# MB1076.net
KiCad netlist of a schematic drawn in Altium Designer
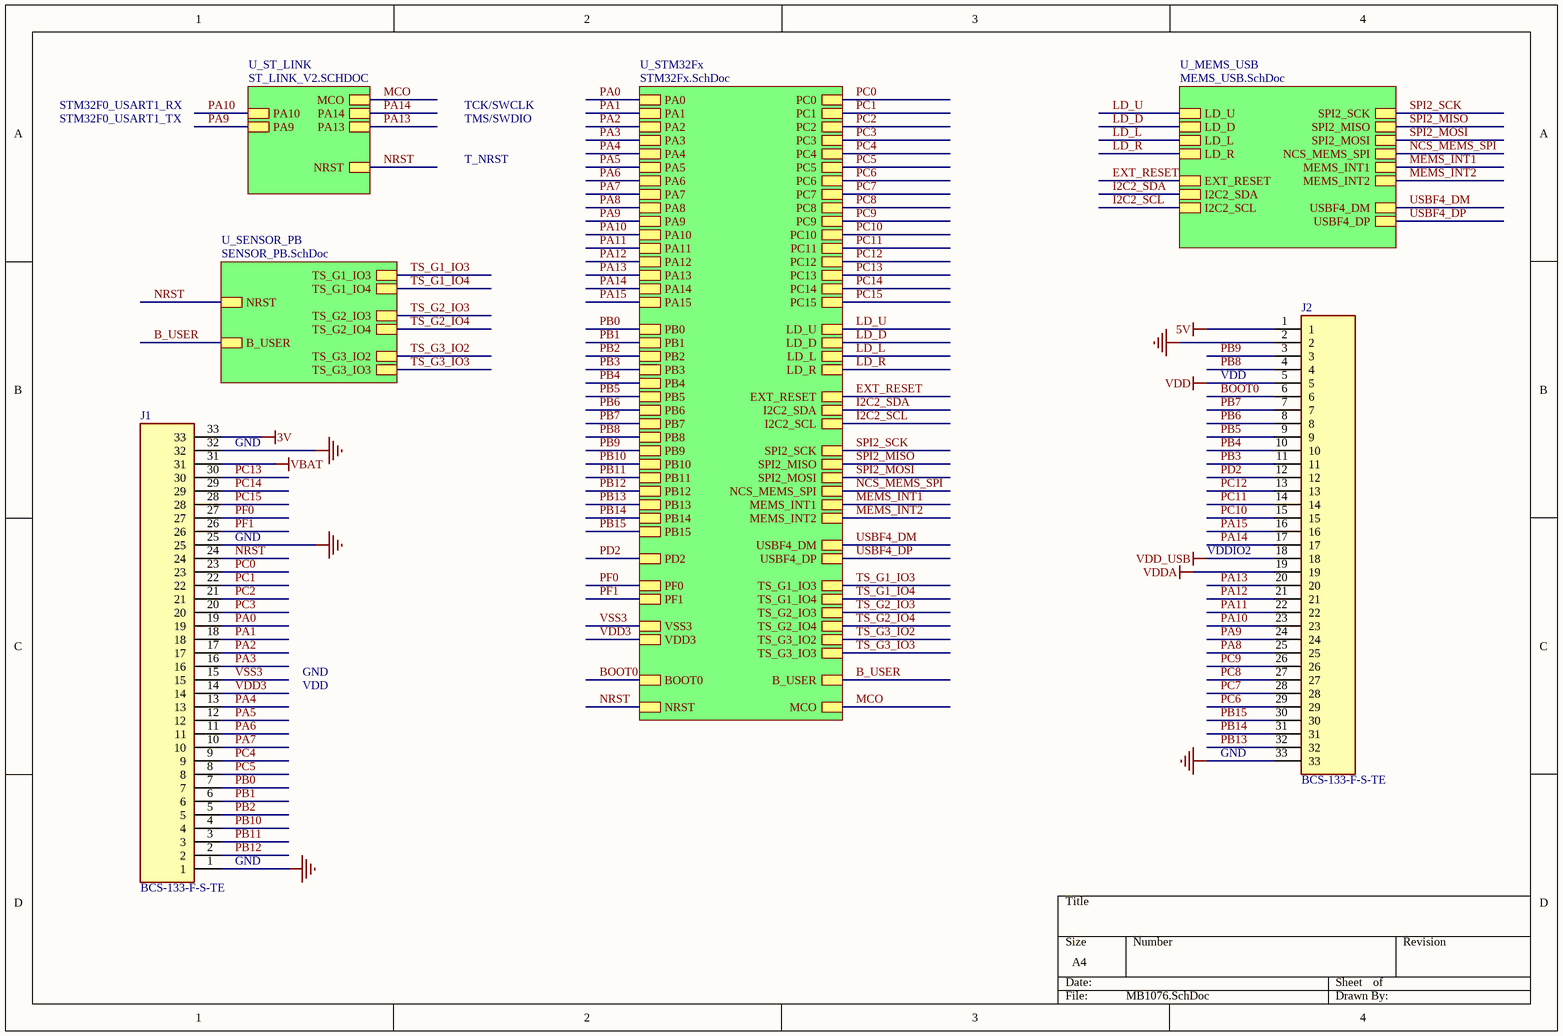
[diagram p0: MB1076.SchDoc]

(export (version "E")
  (design (tool "Eeschema 10.0.6"))
  (components
    (comp (ref "J1")
      (value "BCS-133-F-S-TE")
      (footprint "SamacSys:BCS-133-XXX-S-TE")
      (description "Connector")
      (libsource (lib "*") (part "BCS-133-F-S-TE"))
    )
    (comp (ref "J2")
      (value "BCS-133-F-S-TE")
      (footprint "SamacSys:BCS-133-XXX-S-TE")
      (description "Connector")
      (libsource (lib "") (part "BCS-133-F-S-TE_1"))
    )
  )
  (nets
    (net (code "1") (name "/BOOT0") (class "Default")
      (node (ref "J2") (pin "6") (pinfunction "6_6") (pintype "passive"))
    )
    (net (code "14") (name "/NRST") (class "Default")
      (node (ref "J1") (pin "24") (pinfunction "24_24") (pintype "passive"))
    )
    (net (code "15") (name "/PA0") (class "Default")
      (node (ref "J1") (pin "19") (pinfunction "19_19") (pintype "passive"))
    )
    (net (code "16") (name "/PA1") (class "Default")
      (node (ref "J1") (pin "18") (pinfunction "18_18") (pintype "passive"))
    )
    (net (code "17") (name "/PA2") (class "Default")
      (node (ref "J1") (pin "17") (pinfunction "17_17") (pintype "passive"))
    )
    (net (code "18") (name "/PA3") (class "Default")
      (node (ref "J1") (pin "16") (pinfunction "16_16") (pintype "passive"))
    )
    (net (code "19") (name "/PA4") (class "Default")
      (node (ref "J1") (pin "13") (pinfunction "13_13") (pintype "passive"))
    )
    (net (code "20") (name "/PA5") (class "Default")
      (node (ref "J1") (pin "12") (pinfunction "12_12") (pintype "passive"))
    )
    (net (code "21") (name "/PA6") (class "Default")
      (node (ref "J1") (pin "11") (pinfunction "11_11") (pintype "passive"))
    )
    (net (code "22") (name "/PA7") (class "Default")
      (node (ref "J1") (pin "10") (pinfunction "10_10") (pintype "passive"))
    )
    (net (code "23") (name "/PA8") (class "Default")
      (node (ref "J2") (pin "25") (pinfunction "25_25") (pintype "passive"))
    )
    (net (code "24") (name "/PA9") (class "Default")
      (node (ref "J2") (pin "24") (pinfunction "24_24") (pintype "passive"))
    )
    (net (code "25") (name "/PA10") (class "Default")
      (node (ref "J2") (pin "23") (pinfunction "23_23") (pintype "passive"))
    )
    (net (code "26") (name "/PA11") (class "Default")
      (node (ref "J2") (pin "22") (pinfunction "22_22") (pintype "passive"))
    )
    (net (code "27") (name "/PA12") (class "Default")
      (node (ref "J2") (pin "21") (pinfunction "21_21") (pintype "passive"))
    )
    (net (code "28") (name "/PA13") (class "Default")
      (node (ref "J2") (pin "20") (pinfunction "20_20") (pintype "passive"))
    )
    (net (code "29") (name "/PA14") (class "Default")
      (node (ref "J2") (pin "17") (pinfunction "17_17") (pintype "passive"))
    )
    (net (code "30") (name "/PA15") (class "Default")
      (node (ref "J2") (pin "16") (pinfunction "16_16") (pintype "passive"))
    )
    (net (code "31") (name "/PB0") (class "Default")
      (node (ref "J1") (pin "7") (pinfunction "7_7") (pintype "passive"))
    )
    (net (code "32") (name "/PB1") (class "Default")
      (node (ref "J1") (pin "6") (pinfunction "6_6") (pintype "passive"))
    )
    (net (code "33") (name "/PB2") (class "Default")
      (node (ref "J1") (pin "5") (pinfunction "5_5") (pintype "passive"))
    )
    (net (code "34") (name "/PB3") (class "Default")
      (node (ref "J2") (pin "11") (pinfunction "11_11") (pintype "passive"))
    )
    (net (code "35") (name "/PB4") (class "Default")
      (node (ref "J2") (pin "10") (pinfunction "10_10") (pintype "passive"))
    )
    (net (code "36") (name "/PB5") (class "Default")
      (node (ref "J2") (pin "9") (pinfunction "9_9") (pintype "passive"))
    )
    (net (code "37") (name "/PB6") (class "Default")
      (node (ref "J2") (pin "8") (pinfunction "8_8") (pintype "passive"))
    )
    (net (code "38") (name "/PB7") (class "Default")
      (node (ref "J2") (pin "7") (pinfunction "7_7") (pintype "passive"))
    )
    (net (code "39") (name "/PB8") (class "Default")
      (node (ref "J2") (pin "4") (pinfunction "4_4") (pintype "passive"))
    )
    (net (code "40") (name "/PB9") (class "Default")
      (node (ref "J2") (pin "3") (pinfunction "3_3") (pintype "passive"))
    )
    (net (code "41") (name "/PB10") (class "Default")
      (node (ref "J1") (pin "4") (pinfunction "4_4") (pintype "passive"))
    )
    (net (code "42") (name "/PB11") (class "Default")
      (node (ref "J1") (pin "3") (pinfunction "3_3") (pintype "passive"))
    )
    (net (code "43") (name "/PB12") (class "Default")
      (node (ref "J1") (pin "2") (pinfunction "2_2") (pintype "passive"))
    )
    (net (code "44") (name "/PB13") (class "Default")
      (node (ref "J2") (pin "32") (pinfunction "32_32") (pintype "passive"))
    )
    (net (code "45") (name "/PB14") (class "Default")
      (node (ref "J2") (pin "31") (pinfunction "31_31") (pintype "passive"))
    )
    (net (code "46") (name "/PB15") (class "Default")
      (node (ref "J2") (pin "30") (pinfunction "30_30") (pintype "passive"))
    )
    (net (code "47") (name "/PC0") (class "Default")
      (node (ref "J1") (pin "23") (pinfunction "23_23") (pintype "passive"))
    )
    (net (code "48") (name "/PC1") (class "Default")
      (node (ref "J1") (pin "22") (pinfunction "22_22") (pintype "passive"))
    )
    (net (code "49") (name "/PC2") (class "Default")
      (node (ref "J1") (pin "21") (pinfunction "21_21") (pintype "passive"))
    )
    (net (code "50") (name "/PC3") (class "Default")
      (node (ref "J1") (pin "20") (pinfunction "20_20") (pintype "passive"))
    )
    (net (code "51") (name "/PC4") (class "Default")
      (node (ref "J1") (pin "9") (pinfunction "9_9") (pintype "passive"))
    )
    (net (code "52") (name "/PC5") (class "Default")
      (node (ref "J1") (pin "8") (pinfunction "8_8") (pintype "passive"))
    )
    (net (code "53") (name "/PC6") (class "Default")
      (node (ref "J2") (pin "29") (pinfunction "29_29") (pintype "passive"))
    )
    (net (code "54") (name "/PC7") (class "Default")
      (node (ref "J2") (pin "28") (pinfunction "28_28") (pintype "passive"))
    )
    (net (code "55") (name "/PC8") (class "Default")
      (node (ref "J2") (pin "27") (pinfunction "27_27") (pintype "passive"))
    )
    (net (code "56") (name "/PC9") (class "Default")
      (node (ref "J2") (pin "26") (pinfunction "26_26") (pintype "passive"))
    )
    (net (code "57") (name "/PC10") (class "Default")
      (node (ref "J2") (pin "15") (pinfunction "15_15") (pintype "passive"))
    )
    (net (code "58") (name "/PC11") (class "Default")
      (node (ref "J2") (pin "14") (pinfunction "14_14") (pintype "passive"))
    )
    (net (code "59") (name "/PC12") (class "Default")
      (node (ref "J2") (pin "13") (pinfunction "13_13") (pintype "passive"))
    )
    (net (code "60") (name "/PC13") (class "Default")
      (node (ref "J1") (pin "30") (pinfunction "30_30") (pintype "passive"))
    )
    (net (code "61") (name "/PC14") (class "Default")
      (node (ref "J1") (pin "29") (pinfunction "29_29") (pintype "passive"))
    )
    (net (code "62") (name "/PC15") (class "Default")
      (node (ref "J1") (pin "28") (pinfunction "28_28") (pintype "passive"))
    )
    (net (code "63") (name "/PD2") (class "Default")
      (node (ref "J2") (pin "12") (pinfunction "12_12") (pintype "passive"))
    )
    (net (code "64") (name "/PF0") (class "Default")
      (node (ref "J1") (pin "27") (pinfunction "27_27") (pintype "passive"))
    )
    (net (code "65") (name "/PF1") (class "Default")
      (node (ref "J1") (pin "26") (pinfunction "26_26") (pintype "passive"))
    )
    (net (code "77") (name "/VDD3") (class "Default")
      (node (ref "J1") (pin "14") (pinfunction "14_14") (pintype "passive"))
    )
    (net (code "78") (name "/VSS3") (class "Default")
      (node (ref "J1") (pin "15") (pinfunction "15_15") (pintype "passive"))
    )
    (net (code "79") (name "3V") (class "Default")
      (node (ref "J1") (pin "33") (pinfunction "33_33") (pintype "passive"))
    )
    (net (code "80") (name "5V") (class "Default")
      (node (ref "J2") (pin "1") (pinfunction "1_1") (pintype "passive"))
    )
    (net (code "81") (name "GND") (class "Default")
      (node (ref "J1") (pin "1") (pinfunction "1_1") (pintype "passive"))
      (node (ref "J1") (pin "25") (pinfunction "25_25") (pintype "passive"))
      (node (ref "J1") (pin "32") (pinfunction "32_32") (pintype "passive"))
      (node (ref "J2") (pin "2") (pinfunction "2_2") (pintype "passive"))
      (node (ref "J2") (pin "33") (pinfunction "33_33") (pintype "passive"))
    )
    (net (code "82") (name "VBAT") (class "Default")
      (node (ref "J1") (pin "31") (pinfunction "31_31") (pintype "passive"))
    )
    (net (code "83") (name "VDD") (class "Default")
      (node (ref "J2") (pin "5") (pinfunction "5_5") (pintype "passive"))
    )
    (net (code "84") (name "VDDA") (class "Default")
      (node (ref "J2") (pin "19") (pinfunction "19_19") (pintype "passive"))
    )
    (net (code "85") (name "VDD_USB") (class "Default")
      (node (ref "J2") (pin "18") (pinfunction "18_18") (pintype "passive"))
    )
  )
)
